# emonGLCD_V1_5.net
KiCad netlist of a schematic drawn in EAGLE
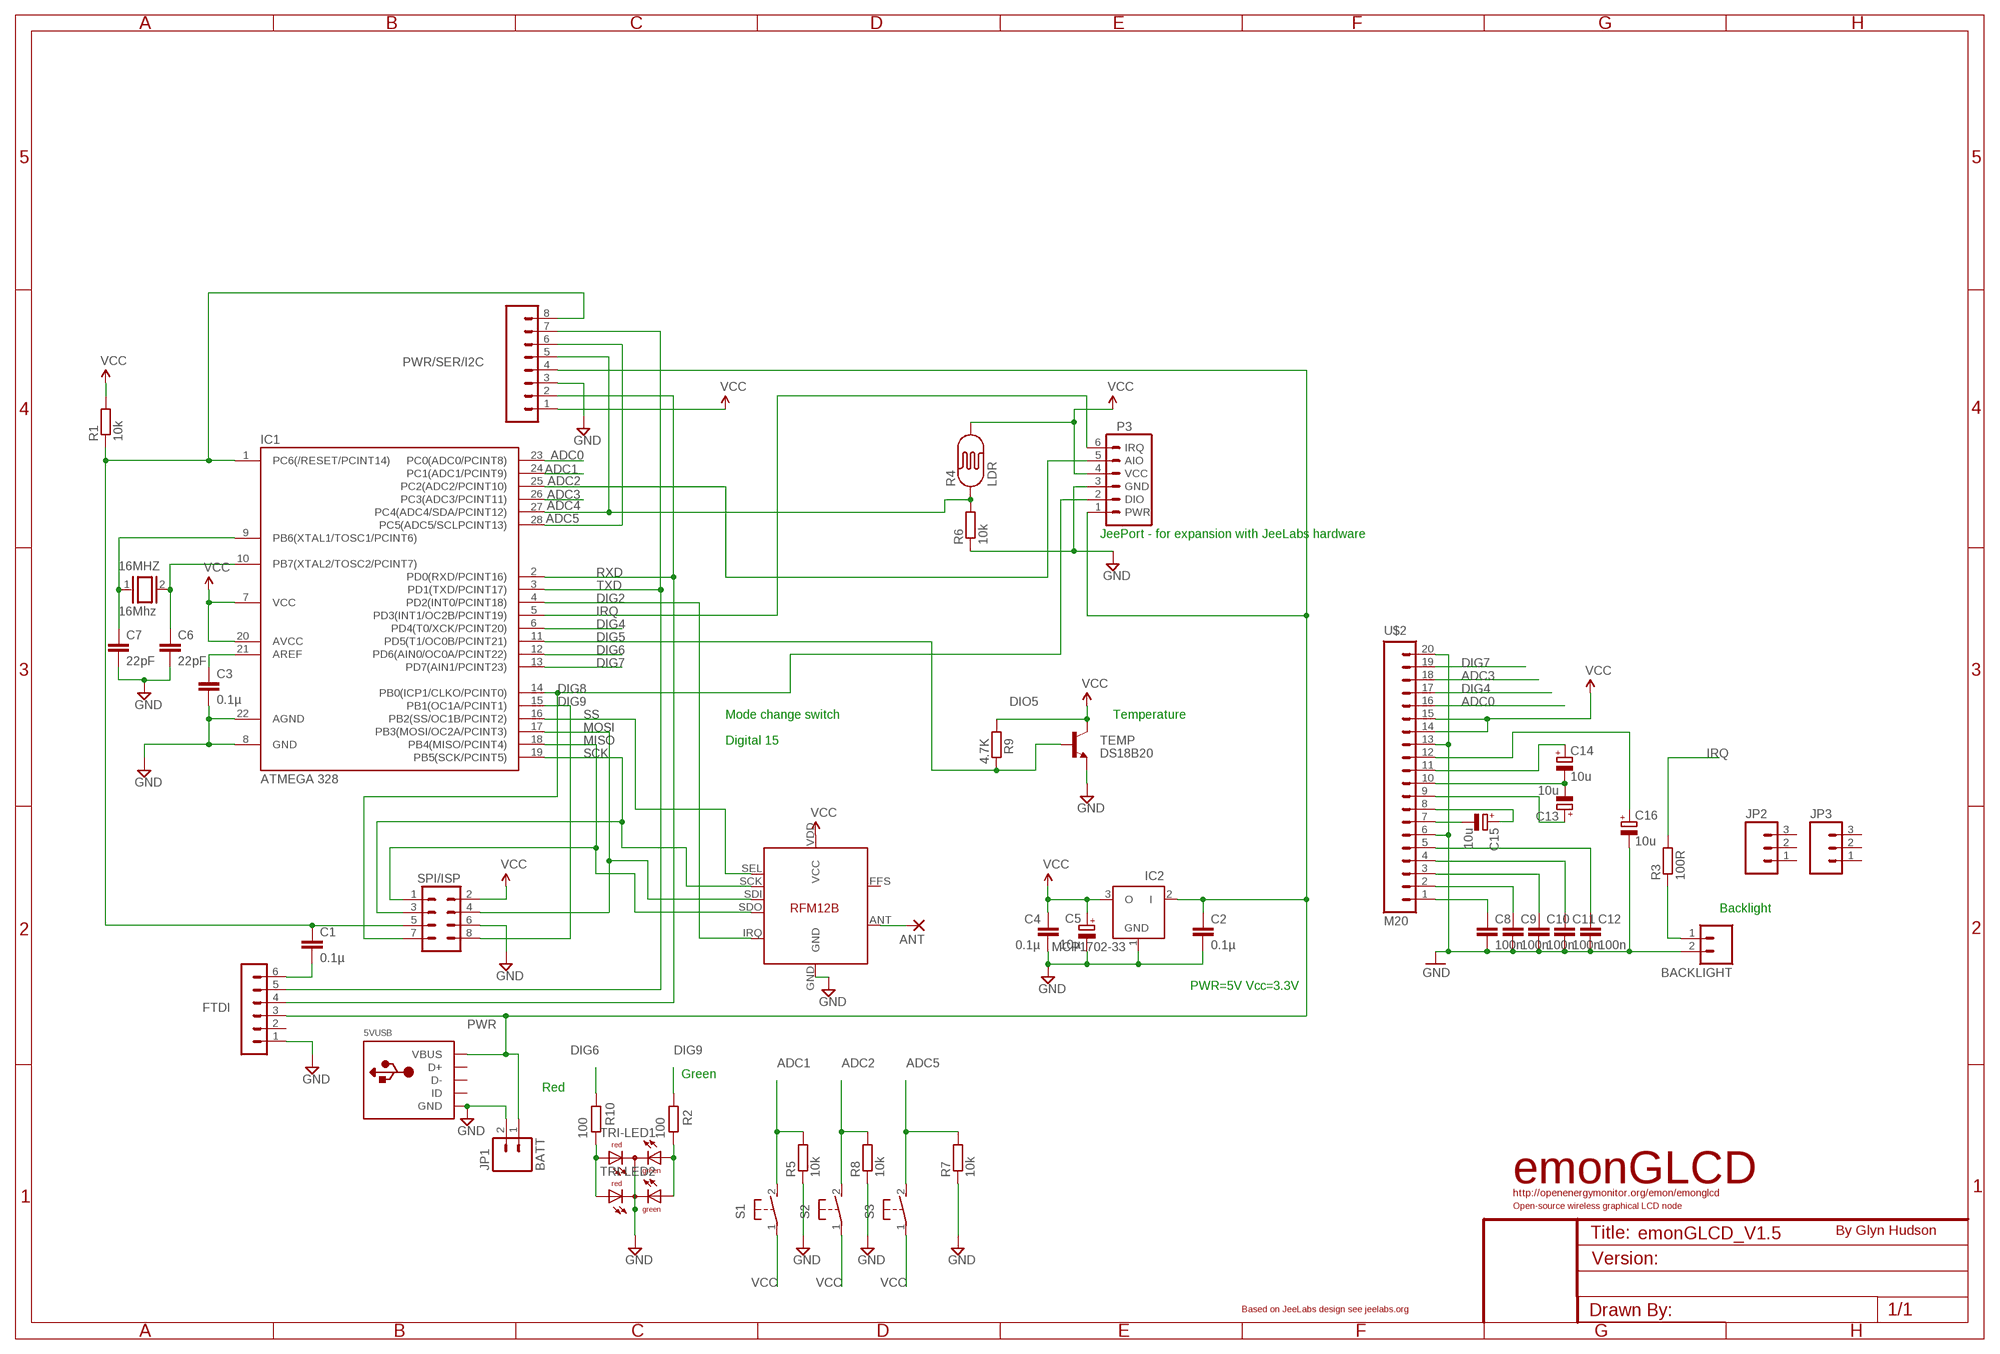
[diagram p0: schematic, sheet 1]

(export (version "E")
  (design (tool "Eeschema 10.0.6"))
  (components
    (comp (ref "5VUSB")
      (value "USBMOLEX")
      (footprint "eagle-import:USB-MINIB-THM-MOLEX")
      (libsource (lib "eagle-import") (part "USBMOLEX"))
    )
    (comp (ref "16MHZ")
      (value "16Mhz")
      (footprint "eagle-import:QS")
      (libsource (lib "eagle-import") (part "XTAL/S"))
    )
    (comp (ref "ANT")
      (value "1,6/0,8")
      (footprint "eagle-import:1,6_0,8")
      (libsource (lib "eagle-import") (part "1,6/0,8"))
    )
    (comp (ref "BACKLIGHT")
      (value "M02PTH")
      (footprint "eagle-import:1X02")
      (libsource (lib "eagle-import") (part "M02PTH"))
    )
    (comp (ref "C1")
      (value "0.1µ")
      (footprint "eagle-import:C025-024X044")
      (libsource (lib "eagle-import") (part "C-EU025-024X044"))
    )
    (comp (ref "C2")
      (value "0.1µ")
      (footprint "eagle-import:C025-024X044")
      (libsource (lib "eagle-import") (part "C-EU025-024X044"))
    )
    (comp (ref "C3")
      (value "0.1µ")
      (footprint "eagle-import:C025-024X044")
      (libsource (lib "eagle-import") (part "C-EU025-024X044"))
    )
    (comp (ref "C4")
      (value "0.1µ")
      (footprint "eagle-import:C025-024X044")
      (libsource (lib "eagle-import") (part "C-EU025-024X044"))
    )
    (comp (ref "C5")
      (value "10µ")
      (footprint "eagle-import:E1,8-4")
      (libsource (lib "eagle-import") (part "CPOL-EUE1.8-4"))
    )
    (comp (ref "C6")
      (value "22pF")
      (footprint "eagle-import:C2.5-2")
      (libsource (lib "eagle-import") (part "C2.5/2"))
    )
    (comp (ref "C7")
      (value "22pF")
      (footprint "eagle-import:C2.5-2")
      (libsource (lib "eagle-import") (part "C2.5/2"))
    )
    (comp (ref "C8")
      (value "100n")
      (footprint "eagle-import:C2.5-2")
      (libsource (lib "eagle-import") (part "C2.5/2"))
    )
    (comp (ref "C9")
      (value "100n")
      (footprint "eagle-import:C2.5-2")
      (libsource (lib "eagle-import") (part "C2.5/2"))
    )
    (comp (ref "C10")
      (value "100n")
      (footprint "eagle-import:C2.5-2")
      (libsource (lib "eagle-import") (part "C2.5/2"))
    )
    (comp (ref "C11")
      (value "100n")
      (footprint "eagle-import:C2.5-2")
      (libsource (lib "eagle-import") (part "C2.5/2"))
    )
    (comp (ref "C12")
      (value "100n")
      (footprint "eagle-import:C2.5-2")
      (libsource (lib "eagle-import") (part "C2.5/2"))
    )
    (comp (ref "C13")
      (value "10u")
      (footprint "eagle-import:E1,8-4")
      (libsource (lib "eagle-import") (part "CPOL-EUE1.8-4"))
    )
    (comp (ref "C14")
      (value "10u")
      (footprint "eagle-import:E1,8-4")
      (libsource (lib "eagle-import") (part "CPOL-EUE1.8-4"))
    )
    (comp (ref "C15")
      (value "10u")
      (footprint "eagle-import:E1,8-4")
      (libsource (lib "eagle-import") (part "CPOL-EUE1.8-4"))
    )
    (comp (ref "C16")
      (value "10u")
      (footprint "eagle-import:E1,8-4")
      (libsource (lib "eagle-import") (part "CPOL-EUE1.8-4"))
    )
    (comp (ref "FTDI")
      (value "FTDI")
      (footprint "eagle-import:MA06-1")
      (libsource (lib "eagle-import") (part "MA06-1"))
    )
    (comp (ref "IC1")
      (value "ATMEGA 328")
      (footprint "eagle-import:DIL28-3")
      (libsource (lib "eagle-import") (part "ATMEGA48/88/168-PU"))
    )
    (comp (ref "IC2")
      (value "MCP1702-33")
      (footprint "eagle-import:TO92")
      (libsource (lib "eagle-import") (part "MCP1702Z"))
    )
    (comp (ref "JP1")
      (value "BATT")
      (footprint "eagle-import:1X02_LOCK_LONGPADS")
      (libsource (lib "eagle-import") (part "M02LOCK_LONGPADS"))
    )
    (comp (ref "JP2")
      (value "M03PTH")
      (footprint "eagle-import:1X03")
      (libsource (lib "eagle-import") (part "M03PTH"))
    )
    (comp (ref "JP3")
      (value "M03PTH")
      (footprint "eagle-import:1X03")
      (libsource (lib "eagle-import") (part "M03PTH"))
    )
    (comp (ref "P3")
      (value "JEEPORT")
      (footprint "eagle-import:PORT6PIN")
      (libsource (lib "eagle-import") (part "JEEPORT-LONGPADS"))
    )
    (comp (ref "PWR/SER/I2C")
      (value "M08")
      (footprint "eagle-import:1X08")
      (libsource (lib "eagle-import") (part "M08"))
    )
    (comp (ref "R1")
      (value "10k")
      (footprint "eagle-import:0204_7")
      (libsource (lib "eagle-import") (part "resistor_R-EU_0204/7"))
    )
    (comp (ref "R2")
      (value "100")
      (footprint "eagle-import:0204_7")
      (libsource (lib "eagle-import") (part "R-EU_0204/7"))
    )
    (comp (ref "R3")
      (value "100R")
      (footprint "eagle-import:0204_7")
      (libsource (lib "eagle-import") (part "R-EU_0204/7"))
    )
    (comp (ref "R4")
      (value "LDR")
      (footprint "eagle-import:PHOTOCELL")
      (libsource (lib "eagle-import") (part "PHOTOCELLPTH"))
    )
    (comp (ref "R5")
      (value "10k")
      (footprint "eagle-import:0204_7")
      (libsource (lib "eagle-import") (part "resistor_R-EU_0204/7"))
    )
    (comp (ref "R6")
      (value "10k")
      (footprint "eagle-import:0204_7")
      (libsource (lib "eagle-import") (part "resistor_R-EU_0204/7"))
    )
    (comp (ref "R7")
      (value "10k")
      (footprint "eagle-import:0204_7")
      (libsource (lib "eagle-import") (part "resistor_R-EU_0204/7"))
    )
    (comp (ref "R8")
      (value "10k")
      (footprint "eagle-import:0204_7")
      (libsource (lib "eagle-import") (part "resistor_R-EU_0204/7"))
    )
    (comp (ref "R9")
      (value "4.7K")
      (footprint "eagle-import:0204_7")
      (libsource (lib "eagle-import") (part "R-EU_0204/7"))
    )
    (comp (ref "R10")
      (value "100")
      (footprint "eagle-import:0204_7")
      (libsource (lib "eagle-import") (part "R-EU_0204/7"))
    )
    (comp (ref "S1")
      (value "31-XX")
      (footprint "eagle-import:B3F-31XX")
      (libsource (lib "eagle-import") (part "31-XX"))
    )
    (comp (ref "S2")
      (value "31-XX")
      (footprint "eagle-import:B3F-31XX")
      (libsource (lib "eagle-import") (part "31-XX"))
    )
    (comp (ref "S3")
      (value "31-XX")
      (footprint "eagle-import:B3F-31XX")
      (libsource (lib "eagle-import") (part "31-XX"))
    )
    (comp (ref "SV7")
      (value "SPI/ISP")
      (footprint "eagle-import:MA04-2")
      (libsource (lib "eagle-import") (part "MA04-2"))
    )
    (comp (ref "TEMP")
      (value "DS18B20")
      (footprint "eagle-import:TO-92")
      (libsource (lib "eagle-import") (part "TRANSISTOR_NPNTO92"))
    )
    (comp (ref "TRI-LED1")
      (value "DUOLED5MM")
      (footprint "eagle-import:DUOLED5MM")
      (libsource (lib "eagle-import") (part "DUOLED5MM"))
    )
    (comp (ref "TRI-LED2")
      (value "DUOLED5MM")
      (footprint "eagle-import:DUOLED5MM")
      (libsource (lib "eagle-import") (part "DUOLED5MM"))
    )
    (comp (ref "U$1")
      (value "RFM12B")
      (footprint "eagle-import:RFM12B")
      (libsource (lib "eagle-import") (part "RFM12B"))
    )
    (comp (ref "U$2")
      (value "M20")
      (footprint "eagle-import:1X20")
      (libsource (lib "eagle-import") (part "M20"))
    )
  )
  (nets
    (net (code "1") (name "/ADC0") (class "Default")
      (node (ref "IC1") (pin "23") (pinfunction "PC0(ADC0/PCINT8)_23") (pintype "bidirectional"))
      (node (ref "U$2") (pin "16") (pinfunction "16_16") (pintype "passive"))
    )
    (net (code "2") (name "/ADC1") (class "Default")
      (node (ref "IC1") (pin "24") (pinfunction "PC1(ADC1/PCINT9)_24") (pintype "bidirectional"))
      (node (ref "R5") (pin "2") (pinfunction "2_2") (pintype "passive"))
      (node (ref "S1") (pin "2") (pinfunction "S_2") (pintype "passive"))
    )
    (net (code "3") (name "/ADC2") (class "Default")
      (node (ref "IC1") (pin "25") (pinfunction "PC2(ADC2/PCINT10)_25") (pintype "bidirectional"))
      (node (ref "P3") (pin "5") (pinfunction "AIO_5") (pintype "bidirectional"))
      (node (ref "R8") (pin "2") (pinfunction "2_2") (pintype "passive"))
      (node (ref "S2") (pin "2") (pinfunction "S_2") (pintype "passive"))
    )
    (net (code "4") (name "/ADC3") (class "Default")
      (node (ref "IC1") (pin "26") (pinfunction "PC3(ADC3/PCINT11)_26") (pintype "bidirectional"))
      (node (ref "U$2") (pin "18") (pinfunction "18_18") (pintype "passive"))
    )
    (net (code "5") (name "/ADC4") (class "Default")
      (node (ref "IC1") (pin "27") (pinfunction "PC4(ADC4/SDA/PCINT12)_27") (pintype "bidirectional"))
      (node (ref "PWR/SER/I2C") (pin "5") (pinfunction "5_5") (pintype "passive"))
      (node (ref "R4") (pin "1") (pinfunction "P$1_1") (pintype "bidirectional"))
      (node (ref "R6") (pin "2") (pinfunction "2_2") (pintype "passive"))
    )
    (net (code "6") (name "/ADC5") (class "Default")
      (node (ref "IC1") (pin "28") (pinfunction "PC5(ADC5/SCLPCINT13)_28") (pintype "bidirectional"))
      (node (ref "PWR/SER/I2C") (pin "6") (pinfunction "6_6") (pintype "passive"))
      (node (ref "R7") (pin "2") (pinfunction "2_2") (pintype "passive"))
      (node (ref "S3") (pin "2") (pinfunction "S_2") (pintype "passive"))
    )
    (net (code "7") (name "/DIG2") (class "Default")
      (node (ref "IC1") (pin "4") (pinfunction "PD2(INT0/PCINT18)_4") (pintype "bidirectional"))
      (node (ref "U$1") (pin "IRQ") (pinfunction "IRQ_IRQ") (pintype "open_collector"))
    )
    (net (code "8") (name "/DIG4") (class "Default")
      (node (ref "IC1") (pin "6") (pinfunction "PD4(T0/XCK/PCINT20)_6") (pintype "bidirectional"))
      (node (ref "U$2") (pin "17") (pinfunction "17_17") (pintype "passive"))
    )
    (net (code "9") (name "/DIG5") (class "Default")
      (node (ref "IC1") (pin "11") (pinfunction "PD5(T1/OC0B/PCINT21)_11") (pintype "bidirectional"))
      (node (ref "R9") (pin "2") (pinfunction "2_2") (pintype "passive"))
      (node (ref "TEMP") (pin "2") (pinfunction "B_2") (pintype "passive"))
    )
    (net (code "10") (name "/DIG6") (class "Default")
      (node (ref "IC1") (pin "12") (pinfunction "PD6(AIN0/OC0A/PCINT22)_12") (pintype "bidirectional"))
      (node (ref "R10") (pin "2") (pinfunction "2_2") (pintype "passive"))
    )
    (net (code "11") (name "/DIG7") (class "Default")
      (node (ref "IC1") (pin "13") (pinfunction "PD7(AIN1/PCINT23)_13") (pintype "bidirectional"))
      (node (ref "U$2") (pin "19") (pinfunction "19_19") (pintype "passive"))
    )
    (net (code "12") (name "/DIG8") (class "Default")
      (node (ref "IC1") (pin "14") (pinfunction "PB0(ICP1/CLKO/PCINT0)_14") (pintype "bidirectional"))
      (node (ref "P3") (pin "2") (pinfunction "DIO_2") (pintype "bidirectional"))
      (node (ref "SV7") (pin "7") (pinfunction "7_7") (pintype "passive"))
    )
    (net (code "13") (name "/DIG9") (class "Default")
      (node (ref "IC1") (pin "15") (pinfunction "PB1(OC1A/PCINT1)_15") (pintype "bidirectional"))
      (node (ref "R2") (pin "2") (pinfunction "2_2") (pintype "passive"))
      (node (ref "SV7") (pin "8") (pinfunction "8_8") (pintype "passive"))
    )
    (net (code "14") (name "/IRQ") (class "Default")
      (node (ref "IC1") (pin "5") (pinfunction "PD3(INT1/OC2B/PCINT19)_5") (pintype "bidirectional"))
      (node (ref "P3") (pin "6") (pinfunction "IRQ_6") (pintype "bidirectional"))
      (node (ref "R3") (pin "2") (pinfunction "2_2") (pintype "passive"))
    )
    (net (code "15") (name "/MISO") (class "Default")
      (node (ref "IC1") (pin "18") (pinfunction "PB4(MISO/PCINT4)_18") (pintype "bidirectional"))
      (node (ref "SV7") (pin "1") (pinfunction "1_1") (pintype "passive"))
      (node (ref "U$1") (pin "SDO") (pinfunction "SDO_SDO") (pintype "output"))
    )
    (net (code "16") (name "/MOSI") (class "Default")
      (node (ref "IC1") (pin "17") (pinfunction "PB3(MOSI/OC2A/PCINT3)_17") (pintype "bidirectional"))
      (node (ref "SV7") (pin "4") (pinfunction "4_4") (pintype "passive"))
      (node (ref "U$1") (pin "SDI") (pinfunction "SDI_SDI") (pintype "input"))
    )
    (net (code "17") (name "/PWR") (class "Default")
      (node (ref "5VUSB") (pin "VBUS") (pinfunction "VBUS_VBUS") (pintype "power_in"))
      (node (ref "C2") (pin "1") (pinfunction "1_1") (pintype "passive"))
      (node (ref "FTDI") (pin "3") (pinfunction "3_3") (pintype "passive"))
      (node (ref "IC2") (pin "2") (pinfunction "I_2") (pintype "input"))
      (node (ref "JP1") (pin "1") (pinfunction "1_1") (pintype "passive"))
      (node (ref "P3") (pin "1") (pinfunction "PWR_1") (pintype "power_in"))
      (node (ref "PWR/SER/I2C") (pin "4") (pinfunction "4_4") (pintype "passive"))
    )
    (net (code "18") (name "/RXD") (class "Default")
      (node (ref "FTDI") (pin "4") (pinfunction "4_4") (pintype "passive"))
      (node (ref "IC1") (pin "2") (pinfunction "PD0(RXD/PCINT16)_2") (pintype "bidirectional"))
      (node (ref "PWR/SER/I2C") (pin "2") (pinfunction "2_2") (pintype "passive"))
    )
    (net (code "19") (name "/SCK") (class "Default")
      (node (ref "IC1") (pin "19") (pinfunction "PB5(SCK/PCINT5)_19") (pintype "bidirectional"))
      (node (ref "SV7") (pin "3") (pinfunction "3_3") (pintype "passive"))
      (node (ref "U$1") (pin "SCK") (pinfunction "SCK_SCK") (pintype "input"))
    )
    (net (code "20") (name "/SS") (class "Default")
      (node (ref "IC1") (pin "16") (pinfunction "PB2(SS/OC1B/PCINT2)_16") (pintype "bidirectional"))
      (node (ref "U$1") (pin "SEL") (pinfunction "SEL_SEL") (pintype "input"))
    )
    (net (code "21") (name "/TXD") (class "Default")
      (node (ref "FTDI") (pin "5") (pinfunction "5_5") (pintype "passive"))
      (node (ref "IC1") (pin "3") (pinfunction "PD1(TXD/PCINT17)_3") (pintype "bidirectional"))
      (node (ref "PWR/SER/I2C") (pin "7") (pinfunction "7_7") (pintype "passive"))
    )
    (net (code "22") (name "GND") (class "Default")
      (node (ref "5VUSB") (pin "GND") (pinfunction "GND_GND") (pintype "power_in"))
      (node (ref "BACKLIGHT") (pin "2") (pinfunction "2_2") (pintype "passive"))
      (node (ref "C10") (pin "2") (pinfunction "2_2") (pintype "passive"))
      (node (ref "C11") (pin "2") (pinfunction "2_2") (pintype "passive"))
      (node (ref "C12") (pin "2") (pinfunction "2_2") (pintype "passive"))
      (node (ref "C16") (pin "-") (pinfunction "-_-") (pintype "passive"))
      (node (ref "C2") (pin "2") (pinfunction "2_2") (pintype "passive"))
      (node (ref "C3") (pin "2") (pinfunction "2_2") (pintype "passive"))
      (node (ref "C4") (pin "2") (pinfunction "2_2") (pintype "passive"))
      (node (ref "C5") (pin "-") (pinfunction "-_-") (pintype "passive"))
      (node (ref "C6") (pin "2") (pinfunction "2_2") (pintype "passive"))
      (node (ref "C7") (pin "2") (pinfunction "2_2") (pintype "passive"))
      (node (ref "C8") (pin "2") (pinfunction "2_2") (pintype "passive"))
      (node (ref "C9") (pin "2") (pinfunction "2_2") (pintype "passive"))
      (node (ref "FTDI") (pin "1") (pinfunction "1_1") (pintype "passive"))
      (node (ref "IC1") (pin "22") (pinfunction "AGND_22") (pintype "power_in"))
      (node (ref "IC1") (pin "8") (pinfunction "GND_8") (pintype "power_in"))
      (node (ref "IC2") (pin "1") (pinfunction "GND_1") (pintype "power_in"))
      (node (ref "JP1") (pin "2") (pinfunction "2_2") (pintype "passive"))
      (node (ref "P3") (pin "3") (pinfunction "GND_3") (pintype "power_in"))
      (node (ref "PWR/SER/I2C") (pin "3") (pinfunction "3_3") (pintype "passive"))
      (node (ref "R5") (pin "1") (pinfunction "1_1") (pintype "passive"))
      (node (ref "R6") (pin "1") (pinfunction "1_1") (pintype "passive"))
      (node (ref "R7") (pin "1") (pinfunction "1_1") (pintype "passive"))
      (node (ref "R8") (pin "1") (pinfunction "1_1") (pintype "passive"))
      (node (ref "SV7") (pin "6") (pinfunction "6_6") (pintype "passive"))
      (node (ref "TEMP") (pin "1") (pinfunction "E_1") (pintype "passive"))
      (node (ref "TRI-LED1") (pin "K") (pinfunction "C_K") (pintype "passive"))
      (node (ref "TRI-LED2") (pin "K") (pinfunction "C_K") (pintype "passive"))
      (node (ref "U$1") (pin "GND") (pinfunction "GND_GND") (pintype "power_in"))
      (node (ref "U$2") (pin "13") (pinfunction "13_13") (pintype "passive"))
      (node (ref "U$2") (pin "20") (pinfunction "20_20") (pintype "passive"))
      (node (ref "U$2") (pin "6") (pinfunction "6_6") (pintype "passive"))
    )
    (net (code "23") (name "Net-(ANT-P)") (class "Default")
      (node (ref "ANT") (pin "1") (pinfunction "P_1") (pintype "passive"))
      (node (ref "U$1") (pin "ANT") (pinfunction "ANT_ANT") (pintype "passive"))
    )
    (net (code "24") (name "Net-(BACKLIGHT-Pad1)") (class "Default")
      (node (ref "BACKLIGHT") (pin "1") (pinfunction "1_1") (pintype "passive"))
      (node (ref "R3") (pin "1") (pinfunction "1_1") (pintype "passive"))
    )
    (net (code "25") (name "Net-(C1-Pad2)") (class "Default")
      (node (ref "C1") (pin "2") (pinfunction "2_2") (pintype "passive"))
      (node (ref "FTDI") (pin "6") (pinfunction "6_6") (pintype "passive"))
    )
    (net (code "26") (name "Net-(C8-Pad1)") (class "Default")
      (node (ref "C8") (pin "1") (pinfunction "1_1") (pintype "passive"))
      (node (ref "U$2") (pin "1") (pinfunction "1_1") (pintype "passive"))
    )
    (net (code "27") (name "Net-(C9-Pad1)") (class "Default")
      (node (ref "C9") (pin "1") (pinfunction "1_1") (pintype "passive"))
      (node (ref "U$2") (pin "2") (pinfunction "2_2") (pintype "passive"))
    )
    (net (code "28") (name "Net-(C10-Pad1)") (class "Default")
      (node (ref "C10") (pin "1") (pinfunction "1_1") (pintype "passive"))
      (node (ref "U$2") (pin "3") (pinfunction "3_3") (pintype "passive"))
    )
    (net (code "29") (name "Net-(C11-Pad1)") (class "Default")
      (node (ref "C11") (pin "1") (pinfunction "1_1") (pintype "passive"))
      (node (ref "U$2") (pin "4") (pinfunction "4_4") (pintype "passive"))
    )
    (net (code "30") (name "Net-(C12-Pad1)") (class "Default")
      (node (ref "C12") (pin "1") (pinfunction "1_1") (pintype "passive"))
      (node (ref "U$2") (pin "5") (pinfunction "5_5") (pintype "passive"))
    )
    (net (code "31") (name "Net-(C13-Pad+)") (class "Default")
      (node (ref "C13") (pin "+") (pinfunction "+_+") (pintype "passive"))
      (node (ref "U$2") (pin "9") (pinfunction "9_9") (pintype "passive"))
    )
    (net (code "32") (name "Net-(C13-Pad-)") (class "Default")
      (node (ref "C13") (pin "-") (pinfunction "-_-") (pintype "passive"))
      (node (ref "C14") (pin "-") (pinfunction "-_-") (pintype "passive"))
      (node (ref "U$2") (pin "10") (pinfunction "10_10") (pintype "passive"))
    )
    (net (code "33") (name "Net-(C14-Pad+)") (class "Default")
      (node (ref "C14") (pin "+") (pinfunction "+_+") (pintype "passive"))
      (node (ref "U$2") (pin "11") (pinfunction "11_11") (pintype "passive"))
    )
    (net (code "34") (name "Net-(C15-Pad+)") (class "Default")
      (node (ref "C15") (pin "+") (pinfunction "+_+") (pintype "passive"))
      (node (ref "U$2") (pin "8") (pinfunction "8_8") (pintype "passive"))
    )
    (net (code "35") (name "Net-(C15-Pad-)") (class "Default")
      (node (ref "C15") (pin "-") (pinfunction "-_-") (pintype "passive"))
      (node (ref "U$2") (pin "7") (pinfunction "7_7") (pintype "passive"))
    )
    (net (code "36") (name "Net-(C16-Pad+)") (class "Default")
      (node (ref "C16") (pin "+") (pinfunction "+_+") (pintype "passive"))
      (node (ref "U$2") (pin "12") (pinfunction "12_12") (pintype "passive"))
    )
    (net (code "37") (name "Net-(IC1-AREF)") (class "Default")
      (node (ref "C3") (pin "1") (pinfunction "1_1") (pintype "passive"))
      (node (ref "IC1") (pin "21") (pinfunction "AREF_21") (pintype "passive"))
    )
    (net (code "38") (name "Net-(IC1-PB6(XTAL1{slash}TOSC1{slash}PCINT6))") (class "Default")
      (node (ref "16MHZ") (pin "1") (pinfunction "1_1") (pintype "passive"))
      (node (ref "C7") (pin "1") (pinfunction "1_1") (pintype "passive"))
      (node (ref "IC1") (pin "9") (pinfunction "PB6(XTAL1/TOSC1/PCINT6)_9") (pintype "bidirectional"))
    )
    (net (code "39") (name "Net-(IC1-PB7(XTAL2{slash}TOSC2{slash}PCINT7))") (class "Default")
      (node (ref "16MHZ") (pin "2") (pinfunction "2_2") (pintype "passive"))
      (node (ref "C6") (pin "1") (pinfunction "1_1") (pintype "passive"))
      (node (ref "IC1") (pin "10") (pinfunction "PB7(XTAL2/TOSC2/PCINT7)_10") (pintype "bidirectional"))
    )
    (net (code "40") (name "Net-(IC1-PC6({slash}RESET{slash}PCINT14))") (class "Default")
      (node (ref "C1") (pin "1") (pinfunction "1_1") (pintype "passive"))
      (node (ref "IC1") (pin "1") (pinfunction "PC6(/RESET/PCINT14)_1") (pintype "bidirectional"))
      (node (ref "PWR/SER/I2C") (pin "8") (pinfunction "8_8") (pintype "passive"))
      (node (ref "R1") (pin "1") (pinfunction "1_1") (pintype "passive"))
      (node (ref "SV7") (pin "5") (pinfunction "5_5") (pintype "passive"))
    )
    (net (code "41") (name "Net-(R2-Pad1)") (class "Default")
      (node (ref "R2") (pin "1") (pinfunction "1_1") (pintype "passive"))
      (node (ref "TRI-LED1") (pin "AG") (pinfunction "AG_AG") (pintype "passive"))
      (node (ref "TRI-LED2") (pin "AG") (pinfunction "AG_AG") (pintype "passive"))
    )
    (net (code "42") (name "Net-(R10-Pad1)") (class "Default")
      (node (ref "R10") (pin "1") (pinfunction "1_1") (pintype "passive"))
      (node (ref "TRI-LED1") (pin "AR") (pinfunction "AR_AR") (pintype "passive"))
      (node (ref "TRI-LED2") (pin "AR") (pinfunction "AR_AR") (pintype "passive"))
    )
    (net (code "43") (name "VCC") (class "Default")
      (node (ref "C4") (pin "1") (pinfunction "1_1") (pintype "passive"))
      (node (ref "C5") (pin "+") (pinfunction "+_+") (pintype "passive"))
      (node (ref "IC1") (pin "20") (pinfunction "AVCC_20") (pintype "passive"))
      (node (ref "IC1") (pin "7") (pinfunction "VCC_7") (pintype "power_in"))
      (node (ref "IC2") (pin "3") (pinfunction "O_3") (pintype "input"))
      (node (ref "P3") (pin "4") (pinfunction "VCC_4") (pintype "power_in"))
      (node (ref "PWR/SER/I2C") (pin "1") (pinfunction "1_1") (pintype "passive"))
      (node (ref "R1") (pin "2") (pinfunction "2_2") (pintype "passive"))
      (node (ref "R4") (pin "2") (pinfunction "P$2_2") (pintype "bidirectional"))
      (node (ref "R9") (pin "1") (pinfunction "1_1") (pintype "passive"))
      (node (ref "S1") (pin "1") (pinfunction "P_1") (pintype "passive"))
      (node (ref "S2") (pin "1") (pinfunction "P_1") (pintype "passive"))
      (node (ref "S3") (pin "1") (pinfunction "P_1") (pintype "passive"))
      (node (ref "SV7") (pin "2") (pinfunction "2_2") (pintype "passive"))
      (node (ref "TEMP") (pin "3") (pinfunction "C_3") (pintype "passive"))
      (node (ref "U$1") (pin "VDD") (pinfunction "VCC_VDD") (pintype "power_in"))
      (node (ref "U$2") (pin "14") (pinfunction "14_14") (pintype "passive"))
      (node (ref "U$2") (pin "15") (pinfunction "15_15") (pintype "passive"))
    )
    (net (code "44") (name "unconnected-(5VUSB-PadD+)") (class "Default")
      (node (ref "5VUSB") (pin "D+") (pinfunction "D+_D+") (pintype "bidirectional"))
    )
    (net (code "45") (name "unconnected-(5VUSB-PadD-)") (class "Default")
      (node (ref "5VUSB") (pin "D-") (pinfunction "D-_D-") (pintype "bidirectional"))
    )
    (net (code "46") (name "unconnected-(5VUSB-PadID)") (class "Default")
      (node (ref "5VUSB") (pin "ID") (pinfunction "ID_ID") (pintype "bidirectional"))
    )
    (net (code "47") (name "unconnected-(FTDI-Pad2)") (class "Default")
      (node (ref "FTDI") (pin "2") (pinfunction "2_2") (pintype "passive"))
    )
    (net (code "48") (name "unconnected-(JP2-Pad1)") (class "Default")
      (node (ref "JP2") (pin "1") (pinfunction "1_1") (pintype "passive"))
    )
    (net (code "49") (name "unconnected-(JP2-Pad2)") (class "Default")
      (node (ref "JP2") (pin "2") (pinfunction "2_2") (pintype "passive"))
    )
    (net (code "50") (name "unconnected-(JP2-Pad3)") (class "Default")
      (node (ref "JP2") (pin "3") (pinfunction "3_3") (pintype "passive"))
    )
    (net (code "51") (name "unconnected-(JP3-Pad1)") (class "Default")
      (node (ref "JP3") (pin "1") (pinfunction "1_1") (pintype "passive"))
    )
    (net (code "52") (name "unconnected-(JP3-Pad2)") (class "Default")
      (node (ref "JP3") (pin "2") (pinfunction "2_2") (pintype "passive"))
    )
    (net (code "53") (name "unconnected-(JP3-Pad3)") (class "Default")
      (node (ref "JP3") (pin "3") (pinfunction "3_3") (pintype "passive"))
    )
    (net (code "54") (name "unconnected-(U$1-PadFFS)") (class "Default")
      (node (ref "U$1") (pin "FFS") (pinfunction "FFS_FFS") (pintype "bidirectional"))
    )
  )
)
